# Schaltplan3.net
KiCad netlist of a schematic drawn in EAGLE
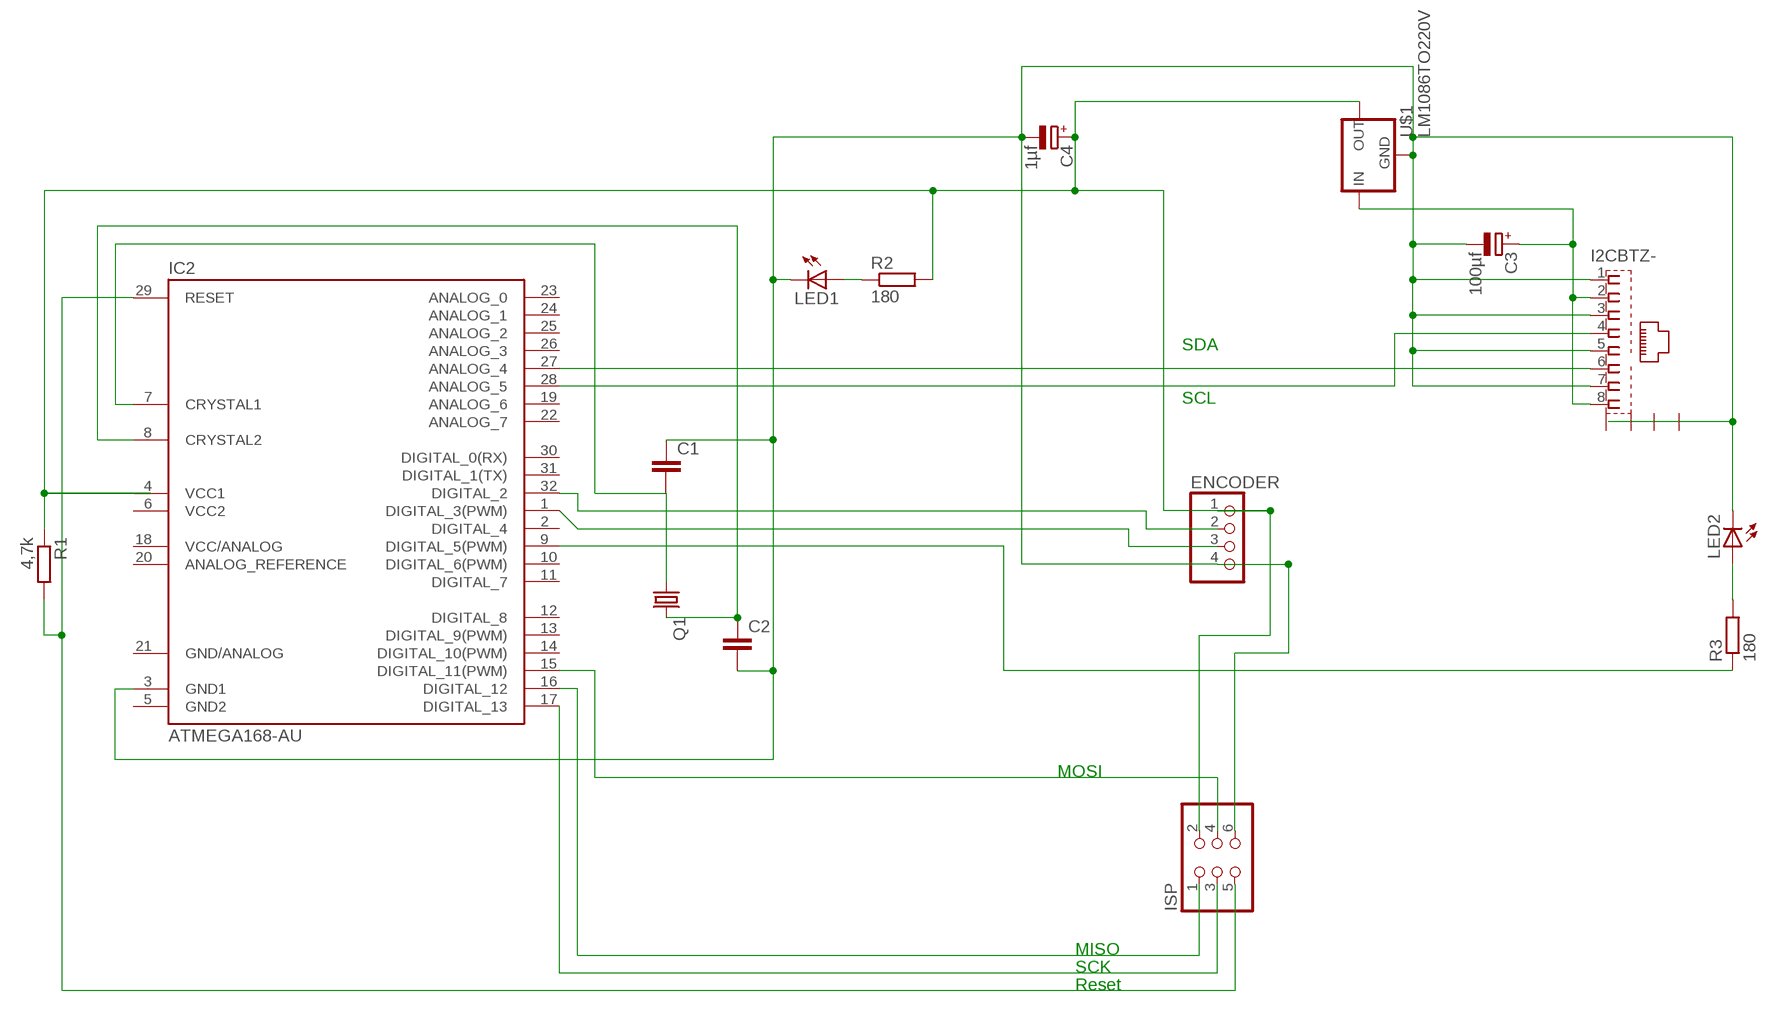
[diagram p0: schematic, sheet 1]

(export (version "E")
  (design (tool "Eeschema 10.0.6"))
  (components
    (comp (ref "C1")
      (value "C-EU025-025X050")
      (footprint "eagle-import:C025-025X050")
      (libsource (lib "eagle-import") (part "C-EU025-025X050"))
    )
    (comp (ref "C2")
      (value "C-EU025-025X050")
      (footprint "eagle-import:C025-025X050")
      (libsource (lib "eagle-import") (part "C-EU025-025X050"))
    )
    (comp (ref "C3")
      (value "100µf")
      (footprint "eagle-import:E2,5-6")
      (libsource (lib "eagle-import") (part "CPOL-EUE2.5-6"))
    )
    (comp (ref "C4")
      (value "1µf")
      (footprint "eagle-import:E2,5-6")
      (libsource (lib "eagle-import") (part "CPOL-EUE2.5-6"))
    )
    (comp (ref "ENCODER")
      (value "PINHD-1X4")
      (footprint "eagle-import:1X04")
      (libsource (lib "eagle-import") (part "PINHD-1X4"))
    )
    (comp (ref "I2CBTZ")
      (value "RJ45")
      (footprint "eagle-import:RJ45")
      (libsource (lib "eagle-import") (part "RJ45"))
    )
    (comp (ref "IC2")
      (value "ATMEGA168-AU")
      (footprint "eagle-import:TQFP32-08")
      (libsource (lib "eagle-import") (part "ATMEGA168-AU"))
    )
    (comp (ref "ISP")
      (value "PINHD-2X3")
      (footprint "eagle-import:2X03")
      (libsource (lib "eagle-import") (part "PINHD-2X3"))
    )
    (comp (ref "LED1")
      (value "LED5MM")
      (footprint "eagle-import:LED5MM")
      (libsource (lib "eagle-import") (part "LED5MM"))
    )
    (comp (ref "LED2")
      (value "LED5MM")
      (footprint "eagle-import:LED5MM")
      (libsource (lib "eagle-import") (part "LED5MM"))
    )
    (comp (ref "Q1")
      (value "CRYSTALHC49S")
      (footprint "eagle-import:HC49_S")
      (libsource (lib "eagle-import") (part "CRYSTALHC49S"))
    )
    (comp (ref "R1")
      (value "4,7k")
      (footprint "eagle-import:0204_7")
      (libsource (lib "eagle-import") (part "R-EU_0204/7"))
    )
    (comp (ref "R2")
      (value "180")
      (footprint "eagle-import:0204_7")
      (libsource (lib "eagle-import") (part "R-EU_0204/7"))
    )
    (comp (ref "R3")
      (value "180")
      (footprint "eagle-import:0204_7")
      (libsource (lib "eagle-import") (part "R-EU_0204/7"))
    )
    (comp (ref "U$1")
      (value "LM1086TO220V")
      (footprint "eagle-import:TO220S")
      (libsource (lib "eagle-import") (part "LM1086TO220V"))
    )
  )
  (nets
    (net (code "1") (name "/GND2") (class "Default")
      (node (ref "IC2") (pin "5") (pinfunction "GND2_5") (pintype "power_in"))
    )
    (net (code "2") (name "/GND{slash}ANALOG") (class "Default")
      (node (ref "IC2") (pin "21") (pinfunction "GND/ANALOG_21") (pintype "power_in"))
    )
    (net (code "3") (name "/VCC2") (class "Default")
      (node (ref "IC2") (pin "6") (pinfunction "VCC2_6") (pintype "power_in"))
    )
    (net (code "4") (name "Net-(IC2-ANALOG_4)") (class "Default")
      (node (ref "I2CBTZ") (pin "6") (pinfunction "6_6") (pintype "passive"))
      (node (ref "IC2") (pin "27") (pinfunction "ANALOG_4_27") (pintype "bidirectional"))
    )
    (net (code "5") (name "Net-(IC2-ANALOG_5)") (class "Default")
      (node (ref "I2CBTZ") (pin "4") (pinfunction "4_4") (pintype "passive"))
      (node (ref "IC2") (pin "28") (pinfunction "ANALOG_5_28") (pintype "bidirectional"))
    )
    (net (code "6") (name "Net-(IC2-CRYSTAL1)") (class "Default")
      (node (ref "C1") (pin "2") (pinfunction "2_2") (pintype "passive"))
      (node (ref "IC2") (pin "7") (pinfunction "CRYSTAL1_7") (pintype "bidirectional"))
      (node (ref "Q1") (pin "1") (pinfunction "1_1") (pintype "passive"))
    )
    (net (code "7") (name "Net-(IC2-CRYSTAL2)") (class "Default")
      (node (ref "C2") (pin "1") (pinfunction "1_1") (pintype "passive"))
      (node (ref "IC2") (pin "8") (pinfunction "CRYSTAL2_8") (pintype "bidirectional"))
      (node (ref "Q1") (pin "2") (pinfunction "2_2") (pintype "passive"))
    )
    (net (code "8") (name "Net-(IC2-DIGITAL_2)") (class "Default")
      (node (ref "ENCODER") (pin "2") (pinfunction "2_2") (pintype "passive"))
      (node (ref "IC2") (pin "32") (pinfunction "DIGITAL_2_32") (pintype "bidirectional"))
    )
    (net (code "9") (name "Net-(IC2-DIGITAL_3(PWM))") (class "Default")
      (node (ref "ENCODER") (pin "3") (pinfunction "3_3") (pintype "passive"))
      (node (ref "IC2") (pin "1") (pinfunction "DIGITAL_3(PWM)_1") (pintype "bidirectional"))
    )
    (net (code "10") (name "Net-(IC2-DIGITAL_5(PWM))") (class "Default")
      (node (ref "IC2") (pin "9") (pinfunction "DIGITAL_5(PWM)_9") (pintype "bidirectional"))
      (node (ref "R3") (pin "1") (pinfunction "1_1") (pintype "passive"))
    )
    (net (code "11") (name "Net-(IC2-DIGITAL_11(PWM))") (class "Default")
      (node (ref "IC2") (pin "15") (pinfunction "DIGITAL_11(PWM)_15") (pintype "bidirectional"))
      (node (ref "ISP") (pin "4") (pinfunction "4_4") (pintype "passive"))
    )
    (net (code "12") (name "Net-(IC2-DIGITAL_12)") (class "Default")
      (node (ref "IC2") (pin "16") (pinfunction "DIGITAL_12_16") (pintype "bidirectional"))
      (node (ref "ISP") (pin "1") (pinfunction "1_1") (pintype "passive"))
    )
    (net (code "13") (name "Net-(IC2-DIGITAL_13)") (class "Default")
      (node (ref "IC2") (pin "17") (pinfunction "DIGITAL_13_17") (pintype "bidirectional"))
      (node (ref "ISP") (pin "3") (pinfunction "3_3") (pintype "passive"))
    )
    (net (code "14") (name "Net-(IC2-GND1)") (class "Default")
      (node (ref "C1") (pin "1") (pinfunction "1_1") (pintype "passive"))
      (node (ref "C2") (pin "2") (pinfunction "2_2") (pintype "passive"))
      (node (ref "C3") (pin "-") (pinfunction "-_-") (pintype "passive"))
      (node (ref "C4") (pin "-") (pinfunction "-_-") (pintype "passive"))
      (node (ref "ENCODER") (pin "4") (pinfunction "4_4") (pintype "passive"))
      (node (ref "I2CBTZ") (pin "1") (pinfunction "1_1") (pintype "passive"))
      (node (ref "I2CBTZ") (pin "3") (pinfunction "3_3") (pintype "passive"))
      (node (ref "I2CBTZ") (pin "5") (pinfunction "5_5") (pintype "passive"))
      (node (ref "I2CBTZ") (pin "7") (pinfunction "7_7") (pintype "passive"))
      (node (ref "IC2") (pin "3") (pinfunction "GND1_3") (pintype "power_in"))
      (node (ref "ISP") (pin "6") (pinfunction "6_6") (pintype "passive"))
      (node (ref "LED1") (pin "K") (pinfunction "C_K") (pintype "passive"))
      (node (ref "LED2") (pin "K") (pinfunction "C_K") (pintype "passive"))
      (node (ref "U$1") (pin "1") (pinfunction "GND_1") (pintype "input"))
    )
    (net (code "15") (name "Net-(IC2-RESET)") (class "Default")
      (node (ref "IC2") (pin "29") (pinfunction "RESET_29") (pintype "bidirectional"))
      (node (ref "ISP") (pin "5") (pinfunction "5_5") (pintype "passive"))
      (node (ref "R1") (pin "2") (pinfunction "2_2") (pintype "passive"))
    )
    (net (code "16") (name "Net-(IC2-VCC1)") (class "Default")
      (node (ref "C4") (pin "+") (pinfunction "+_+") (pintype "passive"))
      (node (ref "ENCODER") (pin "1") (pinfunction "1_1") (pintype "passive"))
      (node (ref "IC2") (pin "4") (pinfunction "VCC1_4") (pintype "power_in"))
      (node (ref "ISP") (pin "2") (pinfunction "2_2") (pintype "passive"))
      (node (ref "R1") (pin "1") (pinfunction "1_1") (pintype "passive"))
      (node (ref "R2") (pin "2") (pinfunction "2_2") (pintype "passive"))
      (node (ref "U$1") (pin "2") (pinfunction "OUT_2") (pintype "passive"))
    )
    (net (code "17") (name "Net-(LED1-PadA)") (class "Default")
      (node (ref "LED1") (pin "A") (pinfunction "A_A") (pintype "passive"))
      (node (ref "R2") (pin "1") (pinfunction "1_1") (pintype "passive"))
    )
    (net (code "18") (name "Net-(LED2-PadA)") (class "Default")
      (node (ref "LED2") (pin "A") (pinfunction "A_A") (pintype "passive"))
      (node (ref "R3") (pin "2") (pinfunction "2_2") (pintype "passive"))
    )
    (net (code "19") (name "Net-(U$1-IN)") (class "Default")
      (node (ref "C3") (pin "+") (pinfunction "+_+") (pintype "passive"))
      (node (ref "I2CBTZ") (pin "2") (pinfunction "2_2") (pintype "passive"))
      (node (ref "I2CBTZ") (pin "8") (pinfunction "8_8") (pintype "passive"))
      (node (ref "U$1") (pin "3") (pinfunction "IN_3") (pintype "input"))
    )
    (net (code "20") (name "unconnected-(I2CBTZB-1-PadG1)") (class "Default")
      (node (ref "I2CBTZ") (pin "G1") (pinfunction "1_G1") (pintype "passive"))
    )
    (net (code "21") (name "unconnected-(I2CBTZC-1-PadG2)") (class "Default")
      (node (ref "I2CBTZ") (pin "G2") (pinfunction "1_G2") (pintype "passive"))
    )
    (net (code "22") (name "unconnected-(I2CBTZD-1-PadG3)") (class "Default")
      (node (ref "I2CBTZ") (pin "G3") (pinfunction "1_G3") (pintype "passive"))
    )
    (net (code "23") (name "unconnected-(I2CBTZE-1-PadG4)") (class "Default")
      (node (ref "I2CBTZ") (pin "G4") (pinfunction "1_G4") (pintype "passive"))
    )
    (net (code "24") (name "unconnected-(IC2-ANALOG_0-Pad23)") (class "Default")
      (node (ref "IC2") (pin "23") (pinfunction "ANALOG_0_23") (pintype "bidirectional"))
    )
    (net (code "25") (name "unconnected-(IC2-ANALOG_1-Pad24)") (class "Default")
      (node (ref "IC2") (pin "24") (pinfunction "ANALOG_1_24") (pintype "bidirectional"))
    )
    (net (code "26") (name "unconnected-(IC2-ANALOG_2-Pad25)") (class "Default")
      (node (ref "IC2") (pin "25") (pinfunction "ANALOG_2_25") (pintype "bidirectional"))
    )
    (net (code "27") (name "unconnected-(IC2-ANALOG_3-Pad26)") (class "Default")
      (node (ref "IC2") (pin "26") (pinfunction "ANALOG_3_26") (pintype "bidirectional"))
    )
    (net (code "28") (name "unconnected-(IC2-ANALOG_6-Pad19)") (class "Default")
      (node (ref "IC2") (pin "19") (pinfunction "ANALOG_6_19") (pintype "passive"))
    )
    (net (code "29") (name "unconnected-(IC2-ANALOG_7-Pad22)") (class "Default")
      (node (ref "IC2") (pin "22") (pinfunction "ANALOG_7_22") (pintype "passive"))
    )
    (net (code "30") (name "unconnected-(IC2-ANALOG_REFERENCE-Pad20)") (class "Default")
      (node (ref "IC2") (pin "20") (pinfunction "ANALOG_REFERENCE_20") (pintype "passive"))
    )
    (net (code "31") (name "unconnected-(IC2-DIGITAL_0(RX)-Pad30)") (class "Default")
      (node (ref "IC2") (pin "30") (pinfunction "DIGITAL_0(RX)_30") (pintype "bidirectional"))
    )
    (net (code "32") (name "unconnected-(IC2-DIGITAL_1(TX)-Pad31)") (class "Default")
      (node (ref "IC2") (pin "31") (pinfunction "DIGITAL_1(TX)_31") (pintype "bidirectional"))
    )
    (net (code "33") (name "unconnected-(IC2-DIGITAL_4-Pad2)") (class "Default")
      (node (ref "IC2") (pin "2") (pinfunction "DIGITAL_4_2") (pintype "bidirectional"))
    )
    (net (code "34") (name "unconnected-(IC2-DIGITAL_6(PWM)-Pad10)") (class "Default")
      (node (ref "IC2") (pin "10") (pinfunction "DIGITAL_6(PWM)_10") (pintype "bidirectional"))
    )
    (net (code "35") (name "unconnected-(IC2-DIGITAL_7-Pad11)") (class "Default")
      (node (ref "IC2") (pin "11") (pinfunction "DIGITAL_7_11") (pintype "bidirectional"))
    )
    (net (code "36") (name "unconnected-(IC2-DIGITAL_8-Pad12)") (class "Default")
      (node (ref "IC2") (pin "12") (pinfunction "DIGITAL_8_12") (pintype "bidirectional"))
    )
    (net (code "37") (name "unconnected-(IC2-DIGITAL_9(PWM)-Pad13)") (class "Default")
      (node (ref "IC2") (pin "13") (pinfunction "DIGITAL_9(PWM)_13") (pintype "bidirectional"))
    )
    (net (code "38") (name "unconnected-(IC2-DIGITAL_10(PWM)-Pad14)") (class "Default")
      (node (ref "IC2") (pin "14") (pinfunction "DIGITAL_10(PWM)_14") (pintype "bidirectional"))
    )
    (net (code "39") (name "unconnected-(IC2-VCC{slash}ANALOG-Pad18)") (class "Default")
      (node (ref "IC2") (pin "18") (pinfunction "VCC/ANALOG_18") (pintype "passive"))
    )
  )
)
